# driver.net
KiCad netlist of a schematic drawn in Altium Designer
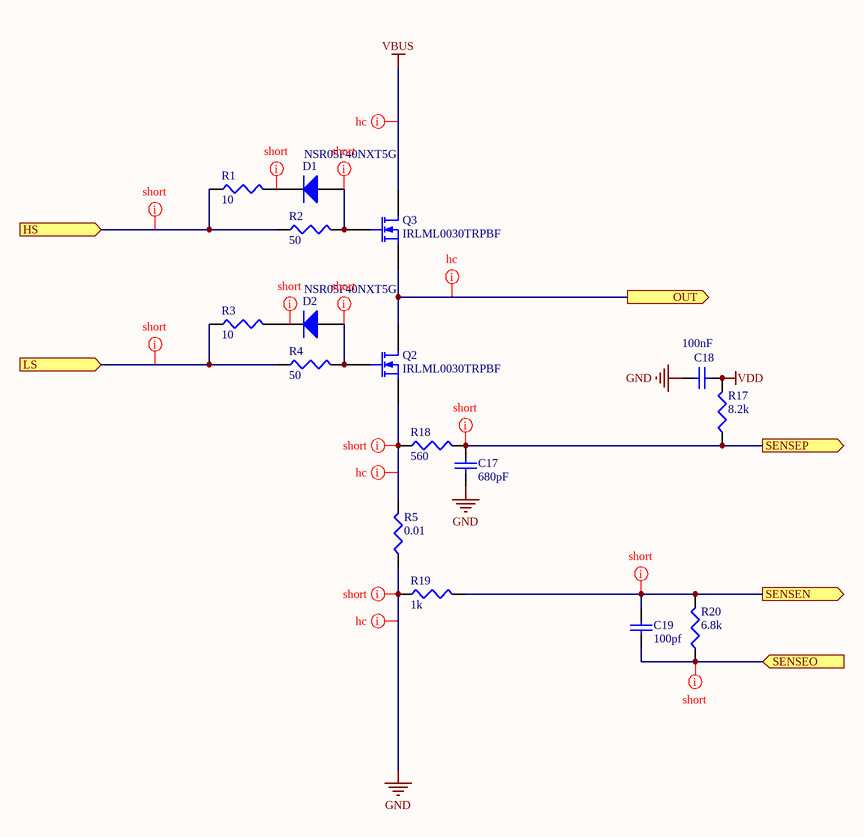
[diagram p0: driver.SchDoc]

(export (version "E")
  (design (tool "Eeschema 10.0.6"))
  (components
    (comp (ref "C17")
      (value "680pF")
      (description "Capacitor")
      (fields (field (name "PUBLISHER") "Altium Limited"))
      (libsource (lib "Miscellaneous Devices") (part "Cap"))
    )
    (comp (ref "C18")
      (value "100nF")
      (description "Capacitor")
      (fields (field (name "PUBLISHER") "Altium Limited"))
      (libsource (lib "Miscellaneous Devices") (part "Cap"))
    )
    (comp (ref "C19")
      (value "100pf")
      (description "Capacitor")
      (fields (field (name "PUBLISHER") "Altium Limited"))
      (libsource (lib "Miscellaneous Devices") (part "Cap"))
    )
    (comp (ref "D1")
      (value "NSR05F40NXT5G")
      (footprint "MY_0402")
      (description "Default Diode")
      (fields (field (name "PUBLISHER") "Altium Limited"))
      (libsource (lib "Miscellaneous Devices") (part "Diode"))
    )
    (comp (ref "D2")
      (value "NSR05F40NXT5G")
      (footprint "MY_0402")
      (description "Default Diode")
      (fields (field (name "PUBLISHER") "Altium Limited"))
      (libsource (lib "Miscellaneous Devices") (part "Diode"))
    )
    (comp (ref "Q2")
      (value "IRLML0030TRPBF")
      (footprint "Micro3")
      (description "N-Channel MOSFET")
      (fields (field (name "PUBLISHER") "Altium Limited"))
      (libsource (lib "Miscellaneous Devices") (part "MOSFET-N"))
    )
    (comp (ref "Q3")
      (value "IRLML0030TRPBF")
      (footprint "Micro3")
      (description "N-Channel MOSFET")
      (fields (field (name "PUBLISHER") "Altium Limited"))
      (libsource (lib "Miscellaneous Devices") (part "MOSFET-N"))
    )
    (comp (ref "R1")
      (value "10")
      (description "Resistor")
      (fields (field (name "PUBLISHER") "Altium Limited"))
      (libsource (lib "Miscellaneous Devices") (part "Res3"))
    )
    (comp (ref "R2")
      (value "50")
      (description "Resistor")
      (fields (field (name "PUBLISHER") "Altium Limited"))
      (libsource (lib "Miscellaneous Devices") (part "Res3"))
    )
    (comp (ref "R3")
      (value "10")
      (description "Resistor")
      (fields (field (name "PUBLISHER") "Altium Limited"))
      (libsource (lib "Miscellaneous Devices") (part "Res3"))
    )
    (comp (ref "R4")
      (value "50")
      (description "Resistor")
      (fields (field (name "PUBLISHER") "Altium Limited"))
      (libsource (lib "Miscellaneous Devices") (part "Res3"))
    )
    (comp (ref "R5")
      (value "0.01")
      (description "Resistor")
      (fields (field (name "PUBLISHER") "Altium Limited"))
      (libsource (lib "Miscellaneous Devices") (part "Res3"))
    )
    (comp (ref "R17")
      (value "8.2k")
      (description "Resistor")
      (fields (field (name "PUBLISHER") "Altium Limited"))
      (libsource (lib "Miscellaneous Devices") (part "Res3"))
    )
    (comp (ref "R18")
      (value "560")
      (description "Resistor")
      (fields (field (name "PUBLISHER") "Altium Limited"))
      (libsource (lib "Miscellaneous Devices") (part "Res3"))
    )
    (comp (ref "R19")
      (value "1k")
      (description "Resistor")
      (fields (field (name "PUBLISHER") "Altium Limited"))
      (libsource (lib "Miscellaneous Devices") (part "Res3"))
    )
    (comp (ref "R20")
      (value "6.8k")
      (description "Resistor")
      (fields (field (name "PUBLISHER") "Altium Limited"))
      (libsource (lib "Miscellaneous Devices") (part "Res3"))
    )
  )
  (nets
    (net (code "1") (name "/HS") (class "Default")
      (node (ref "R1") (pin "1") (pinfunction "1_1") (pintype "passive"))
      (node (ref "R2") (pin "1") (pinfunction "1_1") (pintype "passive"))
    )
    (net (code "2") (name "/LS") (class "Default")
      (node (ref "R3") (pin "1") (pinfunction "1_1") (pintype "passive"))
      (node (ref "R4") (pin "1") (pinfunction "1_1") (pintype "passive"))
    )
    (net (code "3") (name "/OUT") (class "Default")
      (node (ref "Q2") (pin "D") (pinfunction "D_D") (pintype "passive"))
      (node (ref "Q3") (pin "S") (pinfunction "S_S") (pintype "passive"))
    )
    (net (code "4") (name "/SENSEN") (class "Default")
      (node (ref "C19") (pin "1") (pinfunction "1_1") (pintype "passive"))
      (node (ref "R19") (pin "2") (pinfunction "2_2") (pintype "passive"))
      (node (ref "R20") (pin "2") (pinfunction "2_2") (pintype "passive"))
    )
    (net (code "5") (name "/SENSEO") (class "Default")
      (node (ref "C19") (pin "2") (pinfunction "2_2") (pintype "passive"))
      (node (ref "R20") (pin "1") (pinfunction "1_1") (pintype "passive"))
    )
    (net (code "6") (name "/SENSEP") (class "Default")
      (node (ref "C17") (pin "1") (pinfunction "1_1") (pintype "passive"))
      (node (ref "R17") (pin "1") (pinfunction "1_1") (pintype "passive"))
      (node (ref "R18") (pin "2") (pinfunction "2_2") (pintype "passive"))
    )
    (net (code "7") (name "GND") (class "Default")
      (node (ref "C17") (pin "2") (pinfunction "2_2") (pintype "passive"))
      (node (ref "C18") (pin "1") (pinfunction "1_1") (pintype "passive"))
      (node (ref "R19") (pin "1") (pinfunction "1_1") (pintype "passive"))
      (node (ref "R5") (pin "1") (pinfunction "1_1") (pintype "passive"))
    )
    (net (code "8") (name "Net-(D1-A)") (class "Default")
      (node (ref "D1") (pin "1") (pinfunction "A_1") (pintype "passive"))
      (node (ref "Q3") (pin "G") (pinfunction "G_G") (pintype "passive"))
      (node (ref "R2") (pin "2") (pinfunction "2_2") (pintype "passive"))
    )
    (net (code "9") (name "Net-(D1-K)") (class "Default")
      (node (ref "D1") (pin "2") (pinfunction "K_2") (pintype "passive"))
      (node (ref "R1") (pin "2") (pinfunction "2_2") (pintype "passive"))
    )
    (net (code "10") (name "Net-(D2-A)") (class "Default")
      (node (ref "D2") (pin "1") (pinfunction "A_1") (pintype "passive"))
      (node (ref "Q2") (pin "G") (pinfunction "G_G") (pintype "passive"))
      (node (ref "R4") (pin "2") (pinfunction "2_2") (pintype "passive"))
    )
    (net (code "11") (name "Net-(D2-K)") (class "Default")
      (node (ref "D2") (pin "2") (pinfunction "K_2") (pintype "passive"))
      (node (ref "R3") (pin "2") (pinfunction "2_2") (pintype "passive"))
    )
    (net (code "12") (name "Net-(Q2-PadS)") (class "Default")
      (node (ref "Q2") (pin "S") (pinfunction "S_S") (pintype "passive"))
      (node (ref "R18") (pin "1") (pinfunction "1_1") (pintype "passive"))
      (node (ref "R5") (pin "2") (pinfunction "2_2") (pintype "passive"))
    )
    (net (code "13") (name "VBUS") (class "Default")
      (node (ref "Q3") (pin "D") (pinfunction "D_D") (pintype "passive"))
    )
    (net (code "14") (name "VDD") (class "Default")
      (node (ref "C18") (pin "2") (pinfunction "2_2") (pintype "passive"))
      (node (ref "R17") (pin "2") (pinfunction "2_2") (pintype "passive"))
    )
  )
)
